# Page07_CPU_PHY.net
KiCad netlist of a schematic drawn in Altium Designer
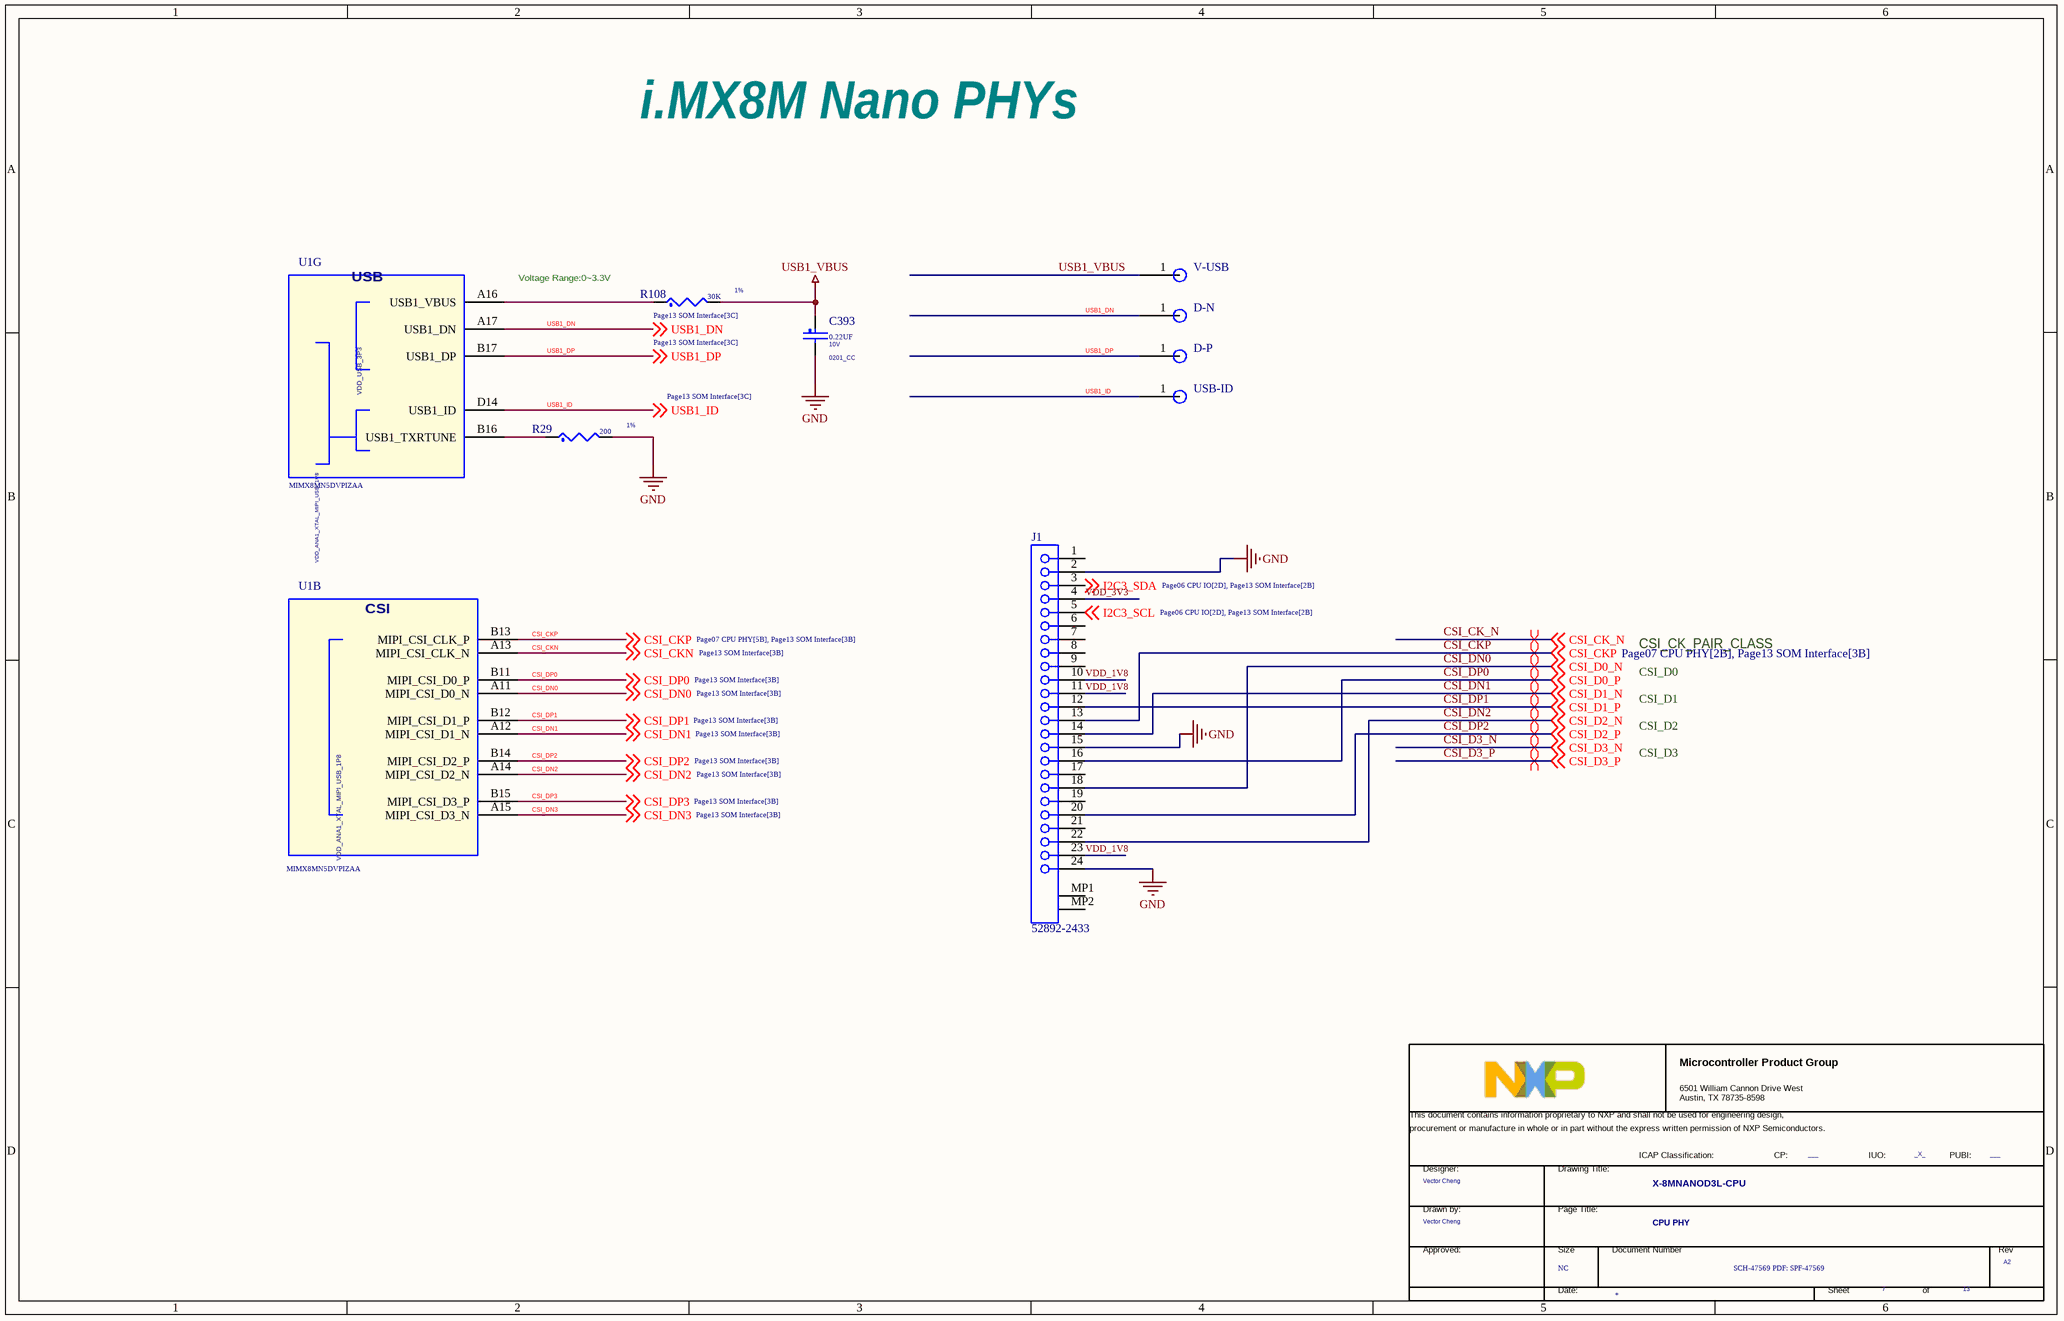
[diagram p0: Page07 CPU PHY.SchDoc]

(export (version "E")
  (design (tool "Eeschema 10.0.6"))
  (components
    (comp (ref "C393")
      (value "0.22UF")
      (footprint "0201_CC - C")
      (description "CAP CER 0.22UF 10V 20% X5R 0201")
      (fields
        (field (name "VOLTAGE") "10V")
        (field (name "TOLERANCE") "20%")
        (field (name "PCB FOOTPRINT") "0201_CC")
      )
      (libsource (lib "*") (part "CAP_NP"))
    )
    (comp (ref "D-N")
      (value "Test Pin1")
      (footprint "Test Pin")
      (libsource (lib "Altium starter project NANO") (part "Test Pin1"))
    )
    (comp (ref "D-P")
      (value "Test Pin1")
      (footprint "Test Pin")
      (libsource (lib "Altium starter project NANO") (part "Test Pin1"))
    )
    (comp (ref "J1")
      (value "52892-2433")
      (footprint "MOLX-52892-2433")
      (fields (field (name "MANUFACTURER") "Molex"))
      (libsource (lib "Altium Content Vault") (part "MOLX-52892-2433"))
    )
    (comp (ref "R29")
      (value "200")
      (footprint "0201_RES")
      (description "RES MF 200 OHM 1/20W 1% 0201")
      (fields (field (name "TOLERANCE") "1%") (field (name "VOLTAGE") "25V"))
      (libsource (lib "*") (part "RES"))
    )
    (comp (ref "R108")
      (value "30K")
      (footprint "0201_RES")
      (description "RES MF 30K 1/20W 1% 0201")
      (fields (field (name "VOLTAGE") "25V") (field (name "TOLERANCE") "1%"))
      (libsource (lib "*") (part "RES"))
    )
    (comp (ref "U1")
      (value "MIMX8MN5DVPIZAA")
      (footprint "BGA306C50P21X21_1100X1100X101")
      (description "IC CPU QUAD CORTEX A53+M7 1.4GHZ -- BGA306")
      (libsource (lib "*") (part "MIMX8MN"))
    )
    (comp (ref "USB-ID")
      (value "Test Pin1")
      (footprint "Test Pin")
      (libsource (lib "Altium starter project NANO") (part "Test Pin1"))
    )
    (comp (ref "V-USB")
      (value "Test Pin1")
      (footprint "Test Pin")
      (libsource (lib "Altium starter project NANO") (part "Test Pin1"))
    )
  )
  (nets
    (net (code "1") (name "/VDD_1V8") (class "Default")
      (node (ref "J1") (pin "10") (pinfunction "10_10") (pintype "passive"))
      (node (ref "J1") (pin "11") (pinfunction "11_11") (pintype "passive"))
      (node (ref "J1") (pin "23") (pinfunction "23_23") (pintype "passive"))
    )
    (net (code "2") (name "/VDD_3V3") (class "Default")
      (node (ref "J1") (pin "4") (pinfunction "4_4") (pintype "passive"))
    )
    (net (code "3") (name "CSI_CKN") (class "Default")
      (node (ref "U1") (pin "A13") (pinfunction "MIPI_CSI_CLK_N_A13") (pintype "passive"))
    )
    (net (code "4") (name "CSI_CKP") (class "Default")
      (node (ref "J1") (pin "13") (pinfunction "13_13") (pintype "passive"))
      (node (ref "U1") (pin "B13") (pinfunction "MIPI_CSI_CLK_P_B13") (pintype "passive"))
    )
    (net (code "6") (name "CSI_D0_N") (class "Default")
      (node (ref "J1") (pin "18") (pinfunction "18_18") (pintype "passive"))
      (node (ref "U1") (pin "A11") (pinfunction "MIPI_CSI_D0_N_A11") (pintype "passive"))
    )
    (net (code "7") (name "CSI_D0_P") (class "Default")
      (node (ref "J1") (pin "16") (pinfunction "16_16") (pintype "passive"))
      (node (ref "U1") (pin "B11") (pinfunction "MIPI_CSI_D0_P_B11") (pintype "passive"))
    )
    (net (code "8") (name "CSI_D1_N") (class "Default")
      (node (ref "J1") (pin "14") (pinfunction "14_14") (pintype "passive"))
      (node (ref "U1") (pin "A12") (pinfunction "MIPI_CSI_D1_N_A12") (pintype "passive"))
    )
    (net (code "9") (name "CSI_D1_P") (class "Default")
      (node (ref "J1") (pin "12") (pinfunction "12_12") (pintype "passive"))
      (node (ref "U1") (pin "B12") (pinfunction "MIPI_CSI_D1_P_B12") (pintype "passive"))
    )
    (net (code "10") (name "CSI_D2_N") (class "Default")
      (node (ref "J1") (pin "22") (pinfunction "22_22") (pintype "passive"))
      (node (ref "U1") (pin "A14") (pinfunction "MIPI_CSI_D2_N_A14") (pintype "passive"))
    )
    (net (code "11") (name "CSI_D2_P") (class "Default")
      (node (ref "J1") (pin "20") (pinfunction "20_20") (pintype "passive"))
      (node (ref "U1") (pin "B14") (pinfunction "MIPI_CSI_D2_P_B14") (pintype "passive"))
    )
    (net (code "14") (name "CSI_DN3") (class "Default")
      (node (ref "U1") (pin "A15") (pinfunction "MIPI_CSI_D3_N_A15") (pintype "passive"))
    )
    (net (code "15") (name "CSI_DP3") (class "Default")
      (node (ref "U1") (pin "B15") (pinfunction "MIPI_CSI_D3_P_B15") (pintype "passive"))
    )
    (net (code "16") (name "GND") (class "Default")
      (node (ref "C393") (pin "2") (pinfunction "2_2") (pintype "passive"))
      (node (ref "J1") (pin "15") (pinfunction "15_15") (pintype "passive"))
      (node (ref "J1") (pin "2") (pinfunction "2_2") (pintype "passive"))
      (node (ref "J1") (pin "24") (pinfunction "24_24") (pintype "passive"))
      (node (ref "R29") (pin "2") (pinfunction "2_2") (pintype "passive"))
    )
    (net (code "17") (name "I2C3_SCL") (class "Default")
      (node (ref "J1") (pin "5") (pinfunction "5_5") (pintype "passive"))
    )
    (net (code "18") (name "I2C3_SDA") (class "Default")
      (node (ref "J1") (pin "3") (pinfunction "3_3") (pintype "passive"))
    )
    (net (code "19") (name "Net-(U1G-USB1_TXRTUNE)") (class "Default")
      (node (ref "R29") (pin "1") (pinfunction "1_1") (pintype "passive"))
      (node (ref "U1") (pin "B16") (pinfunction "USB1_TXRTUNE_B16") (pintype "passive"))
    )
    (net (code "20") (name "Net-(U1G-USB1_VBUS)") (class "Default")
      (node (ref "R108") (pin "1") (pinfunction "1_1") (pintype "passive"))
      (node (ref "U1") (pin "A16") (pinfunction "USB1_VBUS_A16") (pintype "passive"))
    )
    (net (code "21") (name "USB1_DN") (class "Default")
      (node (ref "D-N") (pin "1") (pinfunction "1_1") (pintype "passive"))
      (node (ref "U1") (pin "A17") (pinfunction "USB1_DN_A17") (pintype "passive"))
    )
    (net (code "22") (name "USB1_DP") (class "Default")
      (node (ref "D-P") (pin "1") (pinfunction "1_1") (pintype "passive"))
      (node (ref "U1") (pin "B17") (pinfunction "USB1_DP_B17") (pintype "passive"))
    )
    (net (code "23") (name "USB1_ID") (class "Default")
      (node (ref "U1") (pin "D14") (pinfunction "USB1_ID_D14") (pintype "passive"))
      (node (ref "USB-ID") (pin "1") (pinfunction "1_1") (pintype "passive"))
    )
    (net (code "24") (name "USB1_VBUS") (class "Default")
      (node (ref "C393") (pin "1") (pinfunction "1_1") (pintype "passive"))
      (node (ref "R108") (pin "2") (pinfunction "2_2") (pintype "passive"))
      (node (ref "V-USB") (pin "1") (pinfunction "1_1") (pintype "passive"))
    )
    (net (code "25") (name "unconnected-(J1-Pad1)") (class "Default")
      (node (ref "J1") (pin "1") (pinfunction "1_1") (pintype "passive"))
    )
    (net (code "26") (name "unconnected-(J1-Pad6)") (class "Default")
      (node (ref "J1") (pin "6") (pinfunction "6_6") (pintype "passive"))
    )
    (net (code "27") (name "unconnected-(J1-Pad7)") (class "Default")
      (node (ref "J1") (pin "7") (pinfunction "7_7") (pintype "passive"))
    )
    (net (code "28") (name "unconnected-(J1-Pad8)") (class "Default")
      (node (ref "J1") (pin "8") (pinfunction "8_8") (pintype "passive"))
    )
    (net (code "29") (name "unconnected-(J1-Pad9)") (class "Default")
      (node (ref "J1") (pin "9") (pinfunction "9_9") (pintype "passive"))
    )
    (net (code "30") (name "unconnected-(J1-Pad17)") (class "Default")
      (node (ref "J1") (pin "17") (pinfunction "17_17") (pintype "passive"))
    )
    (net (code "31") (name "unconnected-(J1-Pad19)") (class "Default")
      (node (ref "J1") (pin "19") (pinfunction "19_19") (pintype "passive"))
    )
    (net (code "32") (name "unconnected-(J1-Pad21)") (class "Default")
      (node (ref "J1") (pin "21") (pinfunction "21_21") (pintype "passive"))
    )
    (net (code "33") (name "unconnected-(J1-PadMP1)") (class "Default")
      (node (ref "J1") (pin "MP1") (pinfunction "MP1_MP1") (pintype "passive"))
    )
    (net (code "34") (name "unconnected-(J1-PadMP2)") (class "Default")
      (node (ref "J1") (pin "MP2") (pinfunction "MP2_MP2") (pintype "passive"))
    )
  )
)
